# Group_10.net
KiCad netlist of a schematic drawn in EAGLE
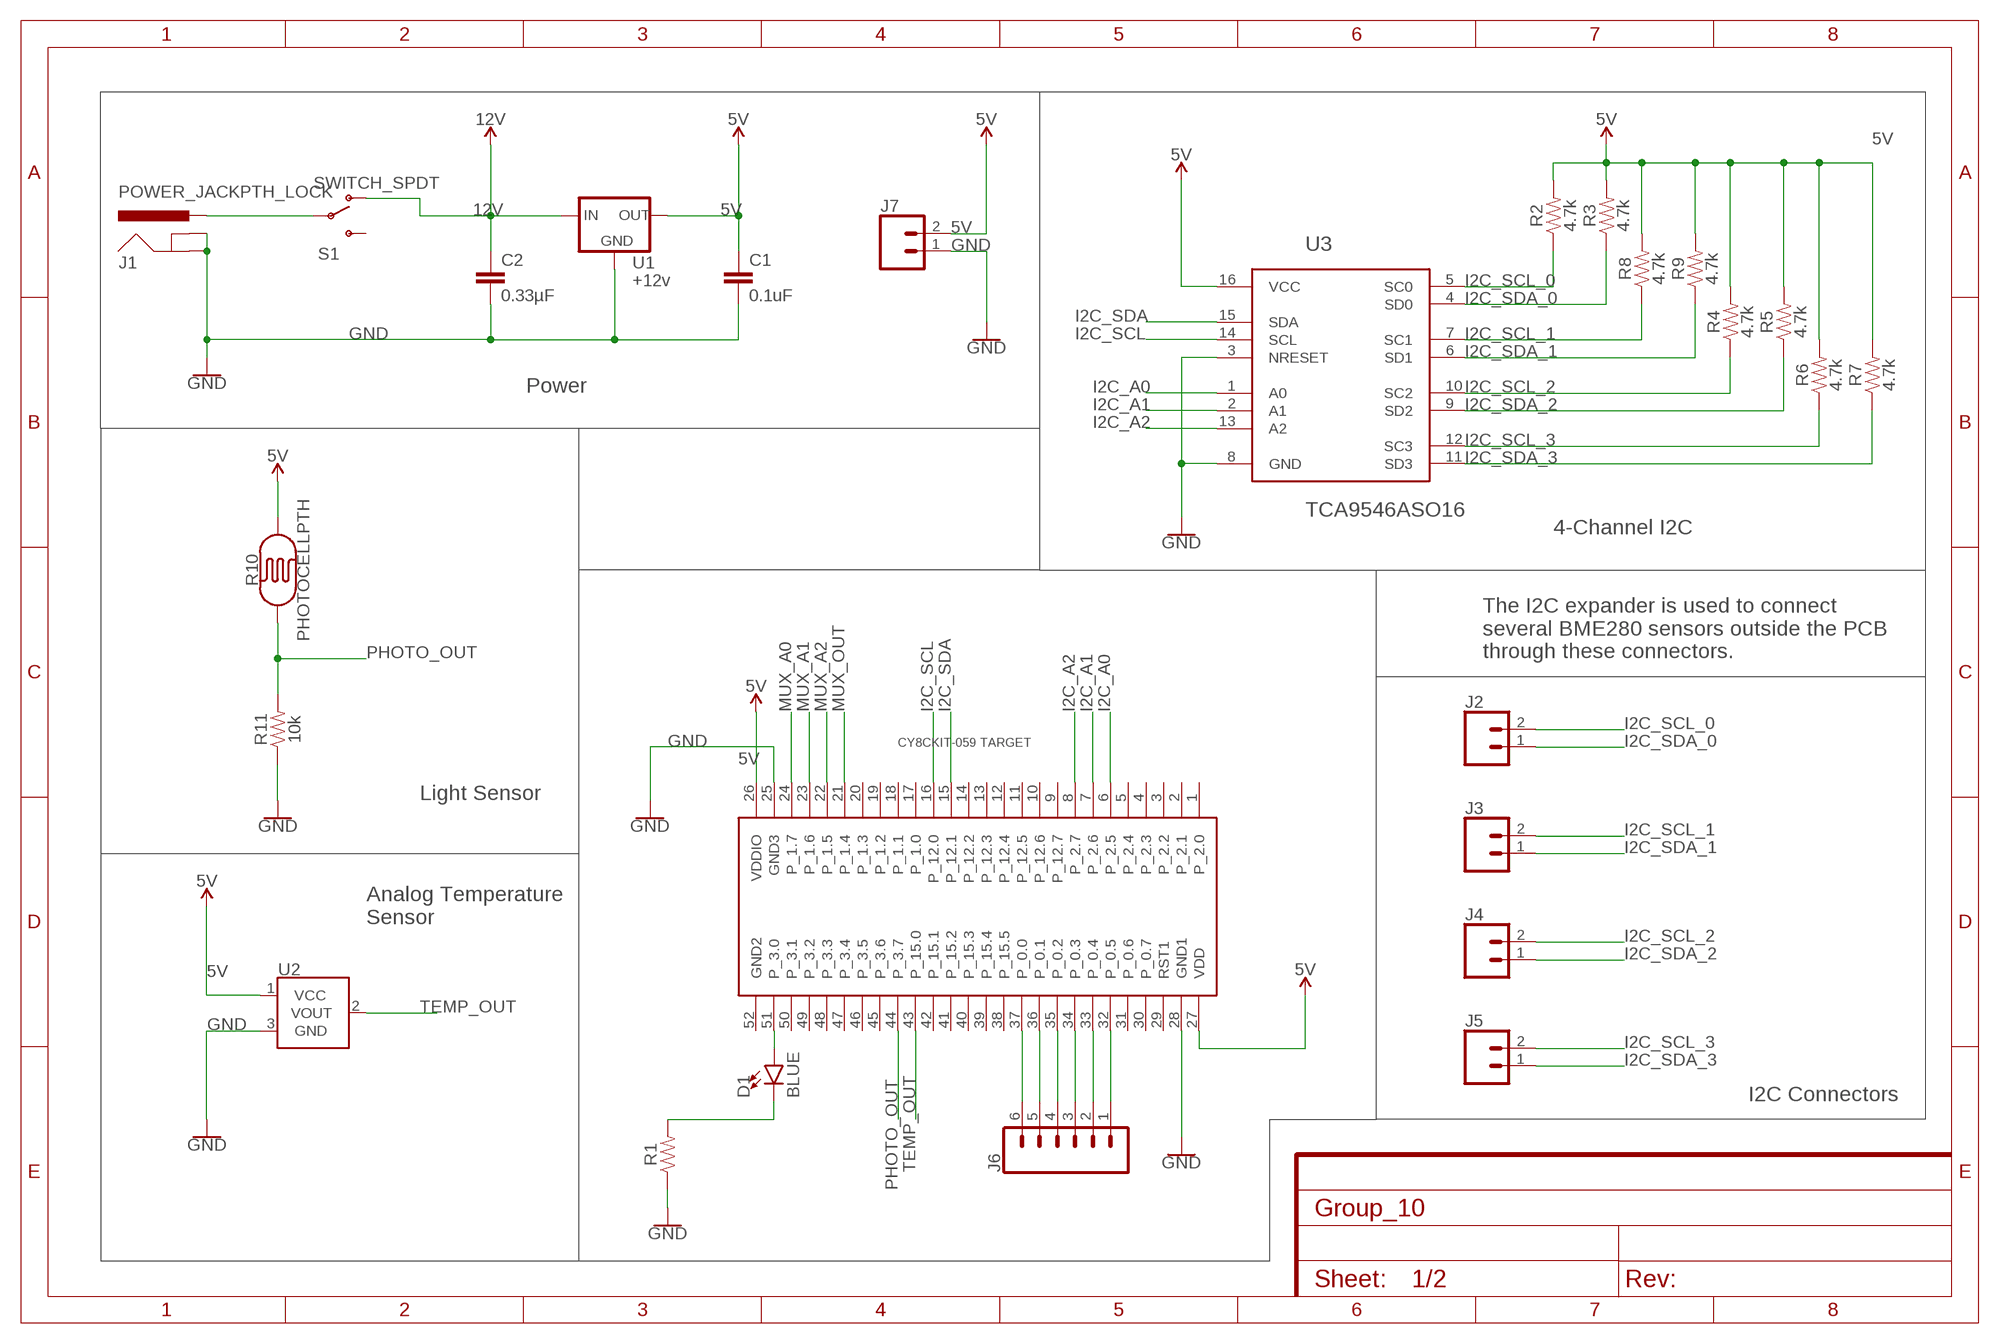
[diagram p0: schematic, sheet 1]
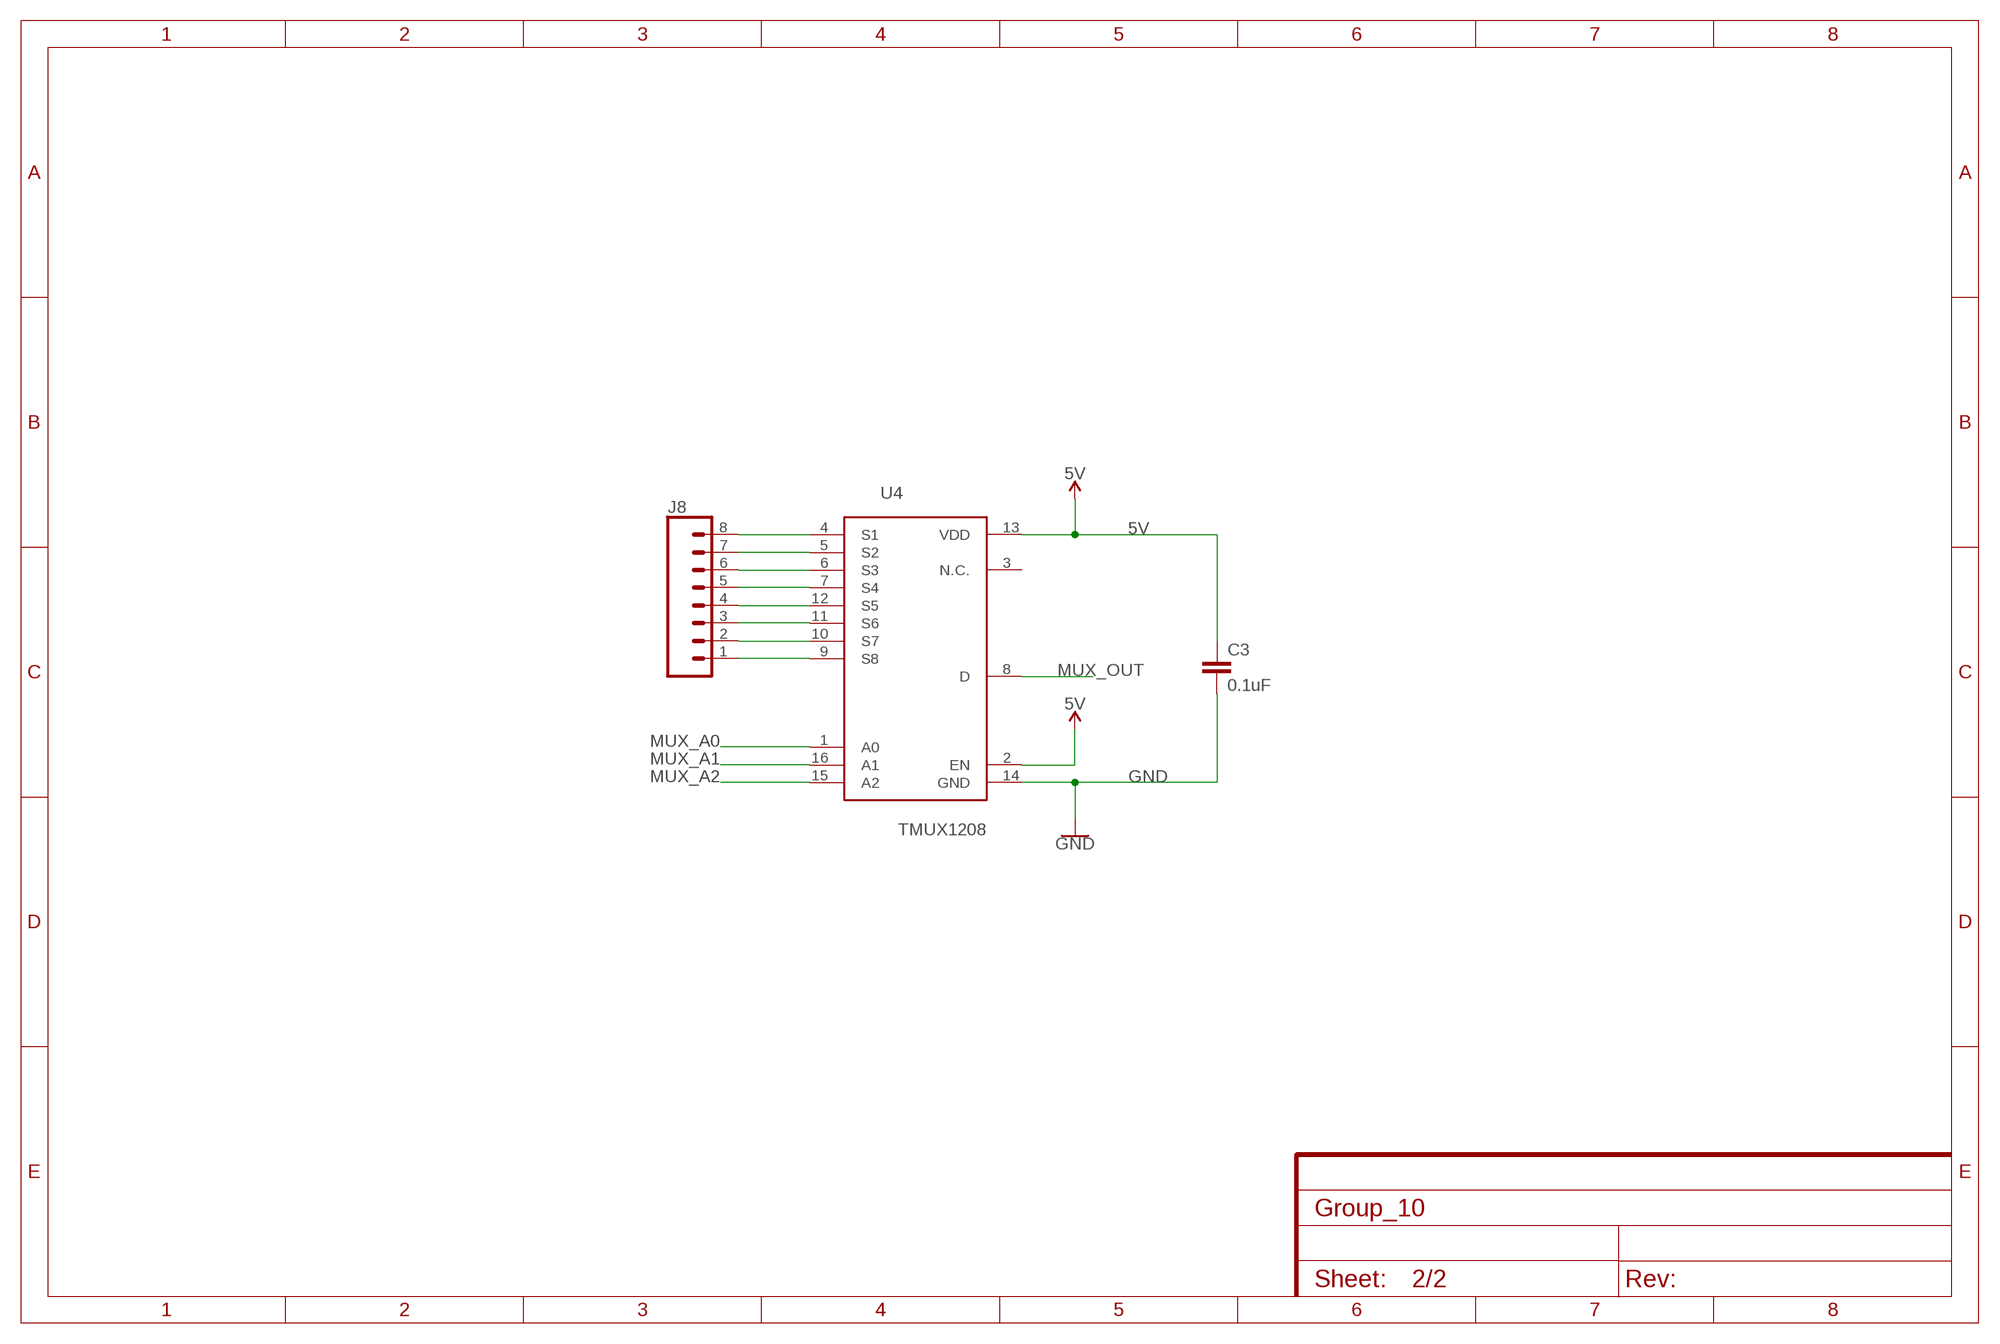
[diagram p1: schematic, sheet 2]

(export (version "E")
  (design (tool "Eeschema 10.0.6"))
  (components
    (comp (ref "C3")
      (value "0.1uF")
      (footprint "eagle-import:CAP-PTH-SMALL-KIT")
      (libsource (lib "eagle-import") (part "0.1UF-KIT-EZ-50V-20%"))
    )
    (comp (ref "J8")
      (value "CONN_08\"")
      (footprint "eagle-import:1X08")
      (libsource (lib "eagle-import") (part "CONN_08{dblquote}"))
    )
    (comp (ref "U4")
      (value "TMUX1208")
      (footprint "eagle-import:QFN16")
      (libsource (lib "eagle-import") (part "TMUX1208"))
    )
    (comp (ref "C1")
      (value "0.1uF")
      (footprint "eagle-import:CAP-PTH-SMALL-KIT")
      (libsource (lib "eagle-import") (part "0.1UF-KIT-EZ-50V-20%"))
    )
    (comp (ref "C2")
      (value "0.33µF")
      (footprint "eagle-import:0805")
      (libsource (lib "eagle-import") (part "0.33UF/330NF-0805-50V-10%"))
    )
    (comp (ref "D1")
      (value "BLUE")
      (footprint "eagle-import:LED-1206")
      (libsource (lib "eagle-import") (part "LED-BLUE1206"))
    )
    (comp (ref "J1")
      (value "POWER_JACKPTH_LOCK")
      (footprint "eagle-import:POWER_JACK_PTH_LOCK")
      (libsource (lib "eagle-import") (part "POWER_JACKPTH_LOCK"))
    )
    (comp (ref "J2")
      (value "CONN_02")
      (footprint "eagle-import:1X02")
      (libsource (lib "eagle-import") (part "CONN_02"))
    )
    (comp (ref "J3")
      (value "CONN_02")
      (footprint "eagle-import:1X02")
      (libsource (lib "eagle-import") (part "CONN_02"))
    )
    (comp (ref "J4")
      (value "CONN_02")
      (footprint "eagle-import:1X02")
      (libsource (lib "eagle-import") (part "CONN_02"))
    )
    (comp (ref "J5")
      (value "CONN_02")
      (footprint "eagle-import:1X02")
      (libsource (lib "eagle-import") (part "CONN_02"))
    )
    (comp (ref "J6")
      (value "CONN_06LOCK")
      (footprint "eagle-import:1X06_LOCK")
      (libsource (lib "eagle-import") (part "CONN_06LOCK"))
    )
    (comp (ref "J7")
      (value "CONN_02")
      (footprint "eagle-import:1X02")
      (libsource (lib "eagle-import") (part "CONN_02"))
    )
    (comp (ref "R1")
      (value "RESISTORAXIAL-0.3")
      (footprint "eagle-import:AXIAL-0.3")
      (libsource (lib "eagle-import") (part "RESISTORAXIAL-0.3"))
    )
    (comp (ref "R2")
      (value "4.7k")
      (footprint "eagle-import:0603")
      (libsource (lib "eagle-import") (part "4.7KOHM-0603-1/10W-1%"))
    )
    (comp (ref "R3")
      (value "4.7k")
      (footprint "eagle-import:0603")
      (libsource (lib "eagle-import") (part "4.7KOHM-0603-1/10W-1%"))
    )
    (comp (ref "R4")
      (value "4.7k")
      (footprint "eagle-import:0603")
      (libsource (lib "eagle-import") (part "4.7KOHM-0603-1/10W-1%"))
    )
    (comp (ref "R5")
      (value "4.7k")
      (footprint "eagle-import:0603")
      (libsource (lib "eagle-import") (part "4.7KOHM-0603-1/10W-1%"))
    )
    (comp (ref "R6")
      (value "4.7k")
      (footprint "eagle-import:0603")
      (libsource (lib "eagle-import") (part "4.7KOHM-0603-1/10W-1%"))
    )
    (comp (ref "R7")
      (value "4.7k")
      (footprint "eagle-import:0603")
      (libsource (lib "eagle-import") (part "4.7KOHM-0603-1/10W-1%"))
    )
    (comp (ref "R8")
      (value "4.7k")
      (footprint "eagle-import:0603")
      (libsource (lib "eagle-import") (part "4.7KOHM-0603-1/10W-1%"))
    )
    (comp (ref "R9")
      (value "4.7k")
      (footprint "eagle-import:0603")
      (libsource (lib "eagle-import") (part "4.7KOHM-0603-1/10W-1%"))
    )
    (comp (ref "R10")
      (value "PHOTOCELLPTH")
      (footprint "eagle-import:PHOTOCELL")
      (libsource (lib "eagle-import") (part "PHOTOCELLPTH"))
    )
    (comp (ref "R11")
      (value "10k")
      (footprint "eagle-import:0603")
      (libsource (lib "eagle-import") (part "10KOHM-0603-1/10W-1%"))
    )
    (comp (ref "S1")
      (value "SWITCH_SPDT")
      (footprint "eagle-import:KPS-1290")
      (libsource (lib "eagle-import") (part "SWITCH_SPDT"))
    )
    (comp (ref "U$2")
      (value "CY8CKIT-059_TARGET_3")
      (footprint "eagle-import:CY8CKIT-059_TARGET_3")
      (libsource (lib "eagle-import") (part "CY8CKIT-059_TARGET_3"))
    )
    (comp (ref "U1")
      (value "+12v")
      (footprint "eagle-import:TO-252")
      (libsource (lib "eagle-import") (part "V_REG_78XX7812"))
    )
    (comp (ref "U2")
      (value "TMP36GT9")
      (footprint "eagle-import:TO-92")
      (libsource (lib "eagle-import") (part "TMP36GT9"))
    )
    (comp (ref "U3")
      (value "TCA9546ASO16")
      (footprint "eagle-import:TSSOP16")
      (libsource (lib "eagle-import") (part "TCA9546ASO16"))
    )
  )
  (nets
    (net (code "1") (name "5V") (class "Default")
      (node (ref "C1") (pin "1") (pinfunction "1_1") (pintype "passive"))
      (node (ref "C3") (pin "1") (pinfunction "1_1") (pintype "passive"))
      (node (ref "J7") (pin "2") (pinfunction "2_2") (pintype "passive"))
      (node (ref "R10") (pin "2") (pinfunction "P$2_2") (pintype "bidirectional"))
      (node (ref "R2") (pin "2") (pinfunction "2_2") (pintype "passive"))
      (node (ref "R3") (pin "2") (pinfunction "2_2") (pintype "passive"))
      (node (ref "R4") (pin "2") (pinfunction "2_2") (pintype "passive"))
      (node (ref "R5") (pin "2") (pinfunction "2_2") (pintype "passive"))
      (node (ref "R6") (pin "2") (pinfunction "2_2") (pintype "passive"))
      (node (ref "R7") (pin "2") (pinfunction "2_2") (pintype "passive"))
      (node (ref "R8") (pin "2") (pinfunction "2_2") (pintype "passive"))
      (node (ref "R9") (pin "2") (pinfunction "2_2") (pintype "passive"))
      (node (ref "U$2") (pin "26") (pinfunction "VDDIO_26") (pintype "power_in"))
      (node (ref "U$2") (pin "27") (pinfunction "VDD_27") (pintype "power_in"))
      (node (ref "U1") (pin "2") (pinfunction "OUT_2") (pintype "passive"))
      (node (ref "U2") (pin "1") (pinfunction "VCC_1") (pintype "bidirectional"))
      (node (ref "U3") (pin "16") (pinfunction "VCC_16") (pintype "bidirectional"))
      (node (ref "U4") (pin "13") (pinfunction "VDD_13") (pintype "bidirectional"))
      (node (ref "U4") (pin "2") (pinfunction "EN_2") (pintype "bidirectional"))
    )
    (net (code "2") (name "12V") (class "Default")
      (node (ref "C2") (pin "1") (pinfunction "1_1") (pintype "passive"))
      (node (ref "S1") (pin "O") (pinfunction "O_O") (pintype "passive"))
      (node (ref "U1") (pin "1") (pinfunction "IN_1") (pintype "input"))
    )
    (net (code "3") (name "GND") (class "Default")
      (node (ref "C1") (pin "2") (pinfunction "2_2") (pintype "passive"))
      (node (ref "C2") (pin "2") (pinfunction "2_2") (pintype "passive"))
      (node (ref "C3") (pin "2") (pinfunction "2_2") (pintype "passive"))
      (node (ref "J1") (pin "GND") (pinfunction "GND_GND") (pintype "bidirectional"))
      (node (ref "J1") (pin "GNDBREAK") (pinfunction "GNDBREAK_GNDBREAK") (pintype "bidirectional"))
      (node (ref "J7") (pin "1") (pinfunction "1_1") (pintype "passive"))
      (node (ref "R1") (pin "P$1") (pinfunction "1_P$1") (pintype "passive"))
      (node (ref "R11") (pin "1") (pinfunction "1_1") (pintype "passive"))
      (node (ref "U$2") (pin "25") (pinfunction "GND3_25") (pintype "power_in"))
      (node (ref "U$2") (pin "28") (pinfunction "GND1_28") (pintype "power_in"))
      (node (ref "U1") (pin "3") (pinfunction "GND_3") (pintype "input"))
      (node (ref "U2") (pin "3") (pinfunction "GND_3") (pintype "bidirectional"))
      (node (ref "U3") (pin "3") (pinfunction "NRESET_3") (pintype "bidirectional"))
      (node (ref "U3") (pin "8") (pinfunction "GND_8") (pintype "bidirectional"))
      (node (ref "U4") (pin "14") (pinfunction "GND_14") (pintype "bidirectional"))
    )
    (net (code "4") (name "GND2") (class "Default")
      (node (ref "U$2") (pin "52") (pinfunction "GND2_52") (pintype "power_in"))
    )
    (net (code "5") (name "I2C_A0") (class "Default")
      (node (ref "U$2") (pin "6") (pinfunction "P_2.5_6") (pintype "bidirectional"))
      (node (ref "U3") (pin "1") (pinfunction "A0_1") (pintype "bidirectional"))
    )
    (net (code "6") (name "I2C_A1") (class "Default")
      (node (ref "U$2") (pin "7") (pinfunction "P_2.6_7") (pintype "bidirectional"))
      (node (ref "U3") (pin "2") (pinfunction "A1_2") (pintype "bidirectional"))
    )
    (net (code "7") (name "I2C_A2") (class "Default")
      (node (ref "U$2") (pin "8") (pinfunction "P_2.7_8") (pintype "bidirectional"))
      (node (ref "U3") (pin "13") (pinfunction "A2_13") (pintype "bidirectional"))
    )
    (net (code "8") (name "I2C_SCL") (class "Default")
      (node (ref "U$2") (pin "16") (pinfunction "P_12.0_16") (pintype "bidirectional"))
      (node (ref "U3") (pin "14") (pinfunction "SCL_14") (pintype "bidirectional"))
    )
    (net (code "9") (name "I2C_SCL_0") (class "Default")
      (node (ref "J2") (pin "2") (pinfunction "2_2") (pintype "passive"))
      (node (ref "R2") (pin "1") (pinfunction "1_1") (pintype "passive"))
      (node (ref "U3") (pin "5") (pinfunction "SC0_5") (pintype "bidirectional"))
    )
    (net (code "10") (name "I2C_SCL_1") (class "Default")
      (node (ref "J3") (pin "2") (pinfunction "2_2") (pintype "passive"))
      (node (ref "R8") (pin "1") (pinfunction "1_1") (pintype "passive"))
      (node (ref "U3") (pin "7") (pinfunction "SC1_7") (pintype "bidirectional"))
    )
    (net (code "11") (name "I2C_SCL_2") (class "Default")
      (node (ref "J4") (pin "2") (pinfunction "2_2") (pintype "passive"))
      (node (ref "R4") (pin "1") (pinfunction "1_1") (pintype "passive"))
      (node (ref "U3") (pin "10") (pinfunction "SC2_10") (pintype "bidirectional"))
    )
    (net (code "12") (name "I2C_SCL_3") (class "Default")
      (node (ref "J5") (pin "2") (pinfunction "2_2") (pintype "passive"))
      (node (ref "R6") (pin "1") (pinfunction "1_1") (pintype "passive"))
      (node (ref "U3") (pin "12") (pinfunction "SC3_12") (pintype "bidirectional"))
    )
    (net (code "13") (name "I2C_SDA") (class "Default")
      (node (ref "U$2") (pin "15") (pinfunction "P_12.1_15") (pintype "bidirectional"))
      (node (ref "U3") (pin "15") (pinfunction "SDA_15") (pintype "bidirectional"))
    )
    (net (code "14") (name "I2C_SDA_0") (class "Default")
      (node (ref "J2") (pin "1") (pinfunction "1_1") (pintype "passive"))
      (node (ref "R3") (pin "1") (pinfunction "1_1") (pintype "passive"))
      (node (ref "U3") (pin "4") (pinfunction "SD0_4") (pintype "bidirectional"))
    )
    (net (code "15") (name "I2C_SDA_1") (class "Default")
      (node (ref "J3") (pin "1") (pinfunction "1_1") (pintype "passive"))
      (node (ref "R9") (pin "1") (pinfunction "1_1") (pintype "passive"))
      (node (ref "U3") (pin "6") (pinfunction "SD1_6") (pintype "bidirectional"))
    )
    (net (code "16") (name "I2C_SDA_2") (class "Default")
      (node (ref "J4") (pin "1") (pinfunction "1_1") (pintype "passive"))
      (node (ref "R5") (pin "1") (pinfunction "1_1") (pintype "passive"))
      (node (ref "U3") (pin "9") (pinfunction "SD2_9") (pintype "bidirectional"))
    )
    (net (code "17") (name "I2C_SDA_3") (class "Default")
      (node (ref "J5") (pin "1") (pinfunction "1_1") (pintype "passive"))
      (node (ref "R7") (pin "1") (pinfunction "1_1") (pintype "passive"))
      (node (ref "U3") (pin "11") (pinfunction "SD3_11") (pintype "bidirectional"))
    )
    (net (code "18") (name "MUX_A0") (class "Default")
      (node (ref "U$2") (pin "24") (pinfunction "P_1.7_24") (pintype "bidirectional"))
      (node (ref "U4") (pin "1") (pinfunction "A0_1") (pintype "bidirectional"))
    )
    (net (code "19") (name "MUX_A1") (class "Default")
      (node (ref "U$2") (pin "23") (pinfunction "P_1.6_23") (pintype "bidirectional"))
      (node (ref "U4") (pin "16") (pinfunction "A1_16") (pintype "bidirectional"))
    )
    (net (code "20") (name "MUX_A2") (class "Default")
      (node (ref "U$2") (pin "22") (pinfunction "P_1.5_22") (pintype "bidirectional"))
      (node (ref "U4") (pin "15") (pinfunction "A2_15") (pintype "bidirectional"))
    )
    (net (code "21") (name "MUX_OUT") (class "Default")
      (node (ref "U$2") (pin "21") (pinfunction "P_1.4_21") (pintype "bidirectional"))
      (node (ref "U4") (pin "8") (pinfunction "D_8") (pintype "bidirectional"))
    )
    (net (code "22") (name "Net-(J1-PadPWR)") (class "Default")
      (node (ref "J1") (pin "PWR") (pinfunction "PWR_PWR") (pintype "bidirectional"))
      (node (ref "S1") (pin "P") (pinfunction "P_P") (pintype "passive"))
    )
    (net (code "23") (name "Net-(R1-2)") (class "Default")
      (node (ref "D1") (pin "C") (pinfunction "C_C") (pintype "passive"))
      (node (ref "R1") (pin "P$2") (pinfunction "2_P$2") (pintype "passive"))
    )
    (net (code "24") (name "Net-(U$2-P_0.0)") (class "Default")
      (node (ref "J6") (pin "6") (pinfunction "6_6") (pintype "passive"))
      (node (ref "U$2") (pin "37") (pinfunction "P_0.0_37") (pintype "bidirectional"))
    )
    (net (code "25") (name "Net-(U$2-P_0.1)") (class "Default")
      (node (ref "J6") (pin "5") (pinfunction "5_5") (pintype "passive"))
      (node (ref "U$2") (pin "36") (pinfunction "P_0.1_36") (pintype "bidirectional"))
    )
    (net (code "26") (name "Net-(U$2-P_0.2)") (class "Default")
      (node (ref "J6") (pin "4") (pinfunction "4_4") (pintype "passive"))
      (node (ref "U$2") (pin "35") (pinfunction "P_0.2_35") (pintype "bidirectional"))
    )
    (net (code "27") (name "Net-(U$2-P_0.3)") (class "Default")
      (node (ref "J6") (pin "3") (pinfunction "3_3") (pintype "passive"))
      (node (ref "U$2") (pin "34") (pinfunction "P_0.3_34") (pintype "bidirectional"))
    )
    (net (code "28") (name "Net-(U$2-P_0.4)") (class "Default")
      (node (ref "J6") (pin "2") (pinfunction "2_2") (pintype "passive"))
      (node (ref "U$2") (pin "33") (pinfunction "P_0.4_33") (pintype "bidirectional"))
    )
    (net (code "29") (name "Net-(U$2-P_0.5)") (class "Default")
      (node (ref "J6") (pin "1") (pinfunction "1_1") (pintype "passive"))
      (node (ref "U$2") (pin "32") (pinfunction "P_0.5_32") (pintype "bidirectional"))
    )
    (net (code "30") (name "Net-(U$2-P_3.0)") (class "Default")
      (node (ref "D1") (pin "A") (pinfunction "A_A") (pintype "passive"))
      (node (ref "U$2") (pin "51") (pinfunction "P_3.0_51") (pintype "bidirectional"))
    )
    (net (code "31") (name "Net-(U4-S1)") (class "Default")
      (node (ref "J8") (pin "8") (pinfunction "8_8") (pintype "passive"))
      (node (ref "U4") (pin "4") (pinfunction "S1_4") (pintype "bidirectional"))
    )
    (net (code "32") (name "Net-(U4-S2)") (class "Default")
      (node (ref "J8") (pin "7") (pinfunction "7_7") (pintype "passive"))
      (node (ref "U4") (pin "5") (pinfunction "S2_5") (pintype "bidirectional"))
    )
    (net (code "33") (name "Net-(U4-S3)") (class "Default")
      (node (ref "J8") (pin "6") (pinfunction "6_6") (pintype "passive"))
      (node (ref "U4") (pin "6") (pinfunction "S3_6") (pintype "bidirectional"))
    )
    (net (code "34") (name "Net-(U4-S4)") (class "Default")
      (node (ref "J8") (pin "5") (pinfunction "5_5") (pintype "passive"))
      (node (ref "U4") (pin "7") (pinfunction "S4_7") (pintype "bidirectional"))
    )
    (net (code "35") (name "Net-(U4-S5)") (class "Default")
      (node (ref "J8") (pin "4") (pinfunction "4_4") (pintype "passive"))
      (node (ref "U4") (pin "12") (pinfunction "S5_12") (pintype "bidirectional"))
    )
    (net (code "36") (name "Net-(U4-S6)") (class "Default")
      (node (ref "J8") (pin "3") (pinfunction "3_3") (pintype "passive"))
      (node (ref "U4") (pin "11") (pinfunction "S6_11") (pintype "bidirectional"))
    )
    (net (code "37") (name "Net-(U4-S7)") (class "Default")
      (node (ref "J8") (pin "2") (pinfunction "2_2") (pintype "passive"))
      (node (ref "U4") (pin "10") (pinfunction "S7_10") (pintype "bidirectional"))
    )
    (net (code "38") (name "Net-(U4-S8)") (class "Default")
      (node (ref "J8") (pin "1") (pinfunction "1_1") (pintype "passive"))
      (node (ref "U4") (pin "9") (pinfunction "S8_9") (pintype "bidirectional"))
    )
    (net (code "39") (name "PHOTO_OUT") (class "Default")
      (node (ref "R10") (pin "1") (pinfunction "P$1_1") (pintype "bidirectional"))
      (node (ref "R11") (pin "2") (pinfunction "2_2") (pintype "passive"))
      (node (ref "U$2") (pin "44") (pinfunction "P_3.7_44") (pintype "bidirectional"))
    )
    (net (code "40") (name "TEMP_OUT") (class "Default")
      (node (ref "U$2") (pin "43") (pinfunction "P_15.0_43") (pintype "bidirectional"))
      (node (ref "U2") (pin "2") (pinfunction "VOUT_2") (pintype "bidirectional"))
    )
    (net (code "41") (name "unconnected-(S1-PadS)") (class "Default")
      (node (ref "S1") (pin "S") (pinfunction "S_S") (pintype "passive"))
    )
    (net (code "42") (name "unconnected-(U$2-P_0.6-Pad31)") (class "Default")
      (node (ref "U$2") (pin "31") (pinfunction "P_0.6_31") (pintype "bidirectional"))
    )
    (net (code "43") (name "unconnected-(U$2-P_0.7-Pad30)") (class "Default")
      (node (ref "U$2") (pin "30") (pinfunction "P_0.7_30") (pintype "bidirectional"))
    )
    (net (code "44") (name "unconnected-(U$2-P_1.0-Pad17)") (class "Default")
      (node (ref "U$2") (pin "17") (pinfunction "P_1.0_17") (pintype "bidirectional"))
    )
    (net (code "45") (name "unconnected-(U$2-P_1.1-Pad18)") (class "Default")
      (node (ref "U$2") (pin "18") (pinfunction "P_1.1_18") (pintype "bidirectional"))
    )
    (net (code "46") (name "unconnected-(U$2-P_1.2-Pad19)") (class "Default")
      (node (ref "U$2") (pin "19") (pinfunction "P_1.2_19") (pintype "bidirectional"))
    )
    (net (code "47") (name "unconnected-(U$2-P_1.3-Pad20)") (class "Default")
      (node (ref "U$2") (pin "20") (pinfunction "P_1.3_20") (pintype "bidirectional"))
    )
    (net (code "48") (name "unconnected-(U$2-P_2.0-Pad1)") (class "Default")
      (node (ref "U$2") (pin "1") (pinfunction "P_2.0_1") (pintype "bidirectional"))
    )
    (net (code "49") (name "unconnected-(U$2-P_2.1-Pad2)") (class "Default")
      (node (ref "U$2") (pin "2") (pinfunction "P_2.1_2") (pintype "bidirectional"))
    )
    (net (code "50") (name "unconnected-(U$2-P_2.2-Pad3)") (class "Default")
      (node (ref "U$2") (pin "3") (pinfunction "P_2.2_3") (pintype "bidirectional"))
    )
    (net (code "51") (name "unconnected-(U$2-P_2.3-Pad4)") (class "Default")
      (node (ref "U$2") (pin "4") (pinfunction "P_2.3_4") (pintype "bidirectional"))
    )
    (net (code "52") (name "unconnected-(U$2-P_2.4-Pad5)") (class "Default")
      (node (ref "U$2") (pin "5") (pinfunction "P_2.4_5") (pintype "bidirectional"))
    )
    (net (code "53") (name "unconnected-(U$2-P_3.1-Pad50)") (class "Default")
      (node (ref "U$2") (pin "50") (pinfunction "P_3.1_50") (pintype "bidirectional"))
    )
    (net (code "54") (name "unconnected-(U$2-P_3.2-Pad49)") (class "Default")
      (node (ref "U$2") (pin "49") (pinfunction "P_3.2_49") (pintype "bidirectional"))
    )
    (net (code "55") (name "unconnected-(U$2-P_3.3-Pad48)") (class "Default")
      (node (ref "U$2") (pin "48") (pinfunction "P_3.3_48") (pintype "bidirectional"))
    )
    (net (code "56") (name "unconnected-(U$2-P_3.4-Pad47)") (class "Default")
      (node (ref "U$2") (pin "47") (pinfunction "P_3.4_47") (pintype "bidirectional"))
    )
    (net (code "57") (name "unconnected-(U$2-P_3.5-Pad46)") (class "Default")
      (node (ref "U$2") (pin "46") (pinfunction "P_3.5_46") (pintype "bidirectional"))
    )
    (net (code "58") (name "unconnected-(U$2-P_3.6-Pad45)") (class "Default")
      (node (ref "U$2") (pin "45") (pinfunction "P_3.6_45") (pintype "bidirectional"))
    )
    (net (code "59") (name "unconnected-(U$2-P_12.2-Pad14)") (class "Default")
      (node (ref "U$2") (pin "14") (pinfunction "P_12.2_14") (pintype "bidirectional"))
    )
    (net (code "60") (name "unconnected-(U$2-P_12.3-Pad13)") (class "Default")
      (node (ref "U$2") (pin "13") (pinfunction "P_12.3_13") (pintype "bidirectional"))
    )
    (net (code "61") (name "unconnected-(U$2-P_12.4-Pad12)") (class "Default")
      (node (ref "U$2") (pin "12") (pinfunction "P_12.4_12") (pintype "bidirectional"))
    )
    (net (code "62") (name "unconnected-(U$2-P_12.5-Pad11)") (class "Default")
      (node (ref "U$2") (pin "11") (pinfunction "P_12.5_11") (pintype "bidirectional"))
    )
    (net (code "63") (name "unconnected-(U$2-P_12.6-Pad10)") (class "Default")
      (node (ref "U$2") (pin "10") (pinfunction "P_12.6_10") (pintype "bidirectional"))
    )
    (net (code "64") (name "unconnected-(U$2-P_12.7-Pad9)") (class "Default")
      (node (ref "U$2") (pin "9") (pinfunction "P_12.7_9") (pintype "bidirectional"))
    )
    (net (code "65") (name "unconnected-(U$2-P_15.1-Pad42)") (class "Default")
      (node (ref "U$2") (pin "42") (pinfunction "P_15.1_42") (pintype "bidirectional"))
    )
    (net (code "66") (name "unconnected-(U$2-P_15.2-Pad41)") (class "Default")
      (node (ref "U$2") (pin "41") (pinfunction "P_15.2_41") (pintype "bidirectional"))
    )
    (net (code "67") (name "unconnected-(U$2-P_15.3-Pad40)") (class "Default")
      (node (ref "U$2") (pin "40") (pinfunction "P_15.3_40") (pintype "bidirectional"))
    )
    (net (code "68") (name "unconnected-(U$2-P_15.4-Pad39)") (class "Default")
      (node (ref "U$2") (pin "39") (pinfunction "P_15.4_39") (pintype "bidirectional"))
    )
    (net (code "69") (name "unconnected-(U$2-P_15.5-Pad38)") (class "Default")
      (node (ref "U$2") (pin "38") (pinfunction "P_15.5_38") (pintype "bidirectional"))
    )
    (net (code "70") (name "unconnected-(U$2-RST1-Pad29)") (class "Default")
      (node (ref "U$2") (pin "29") (pinfunction "RST1_29") (pintype "bidirectional"))
    )
    (net (code "71") (name "unconnected-(U4-N.C.-Pad3)") (class "Default")
      (node (ref "U4") (pin "3") (pinfunction "N.C._3") (pintype "bidirectional"))
    )
  )
)
